# USB_Flash_Drive_Replacer.net
KiCad netlist of a schematic drawn in EasyEDA
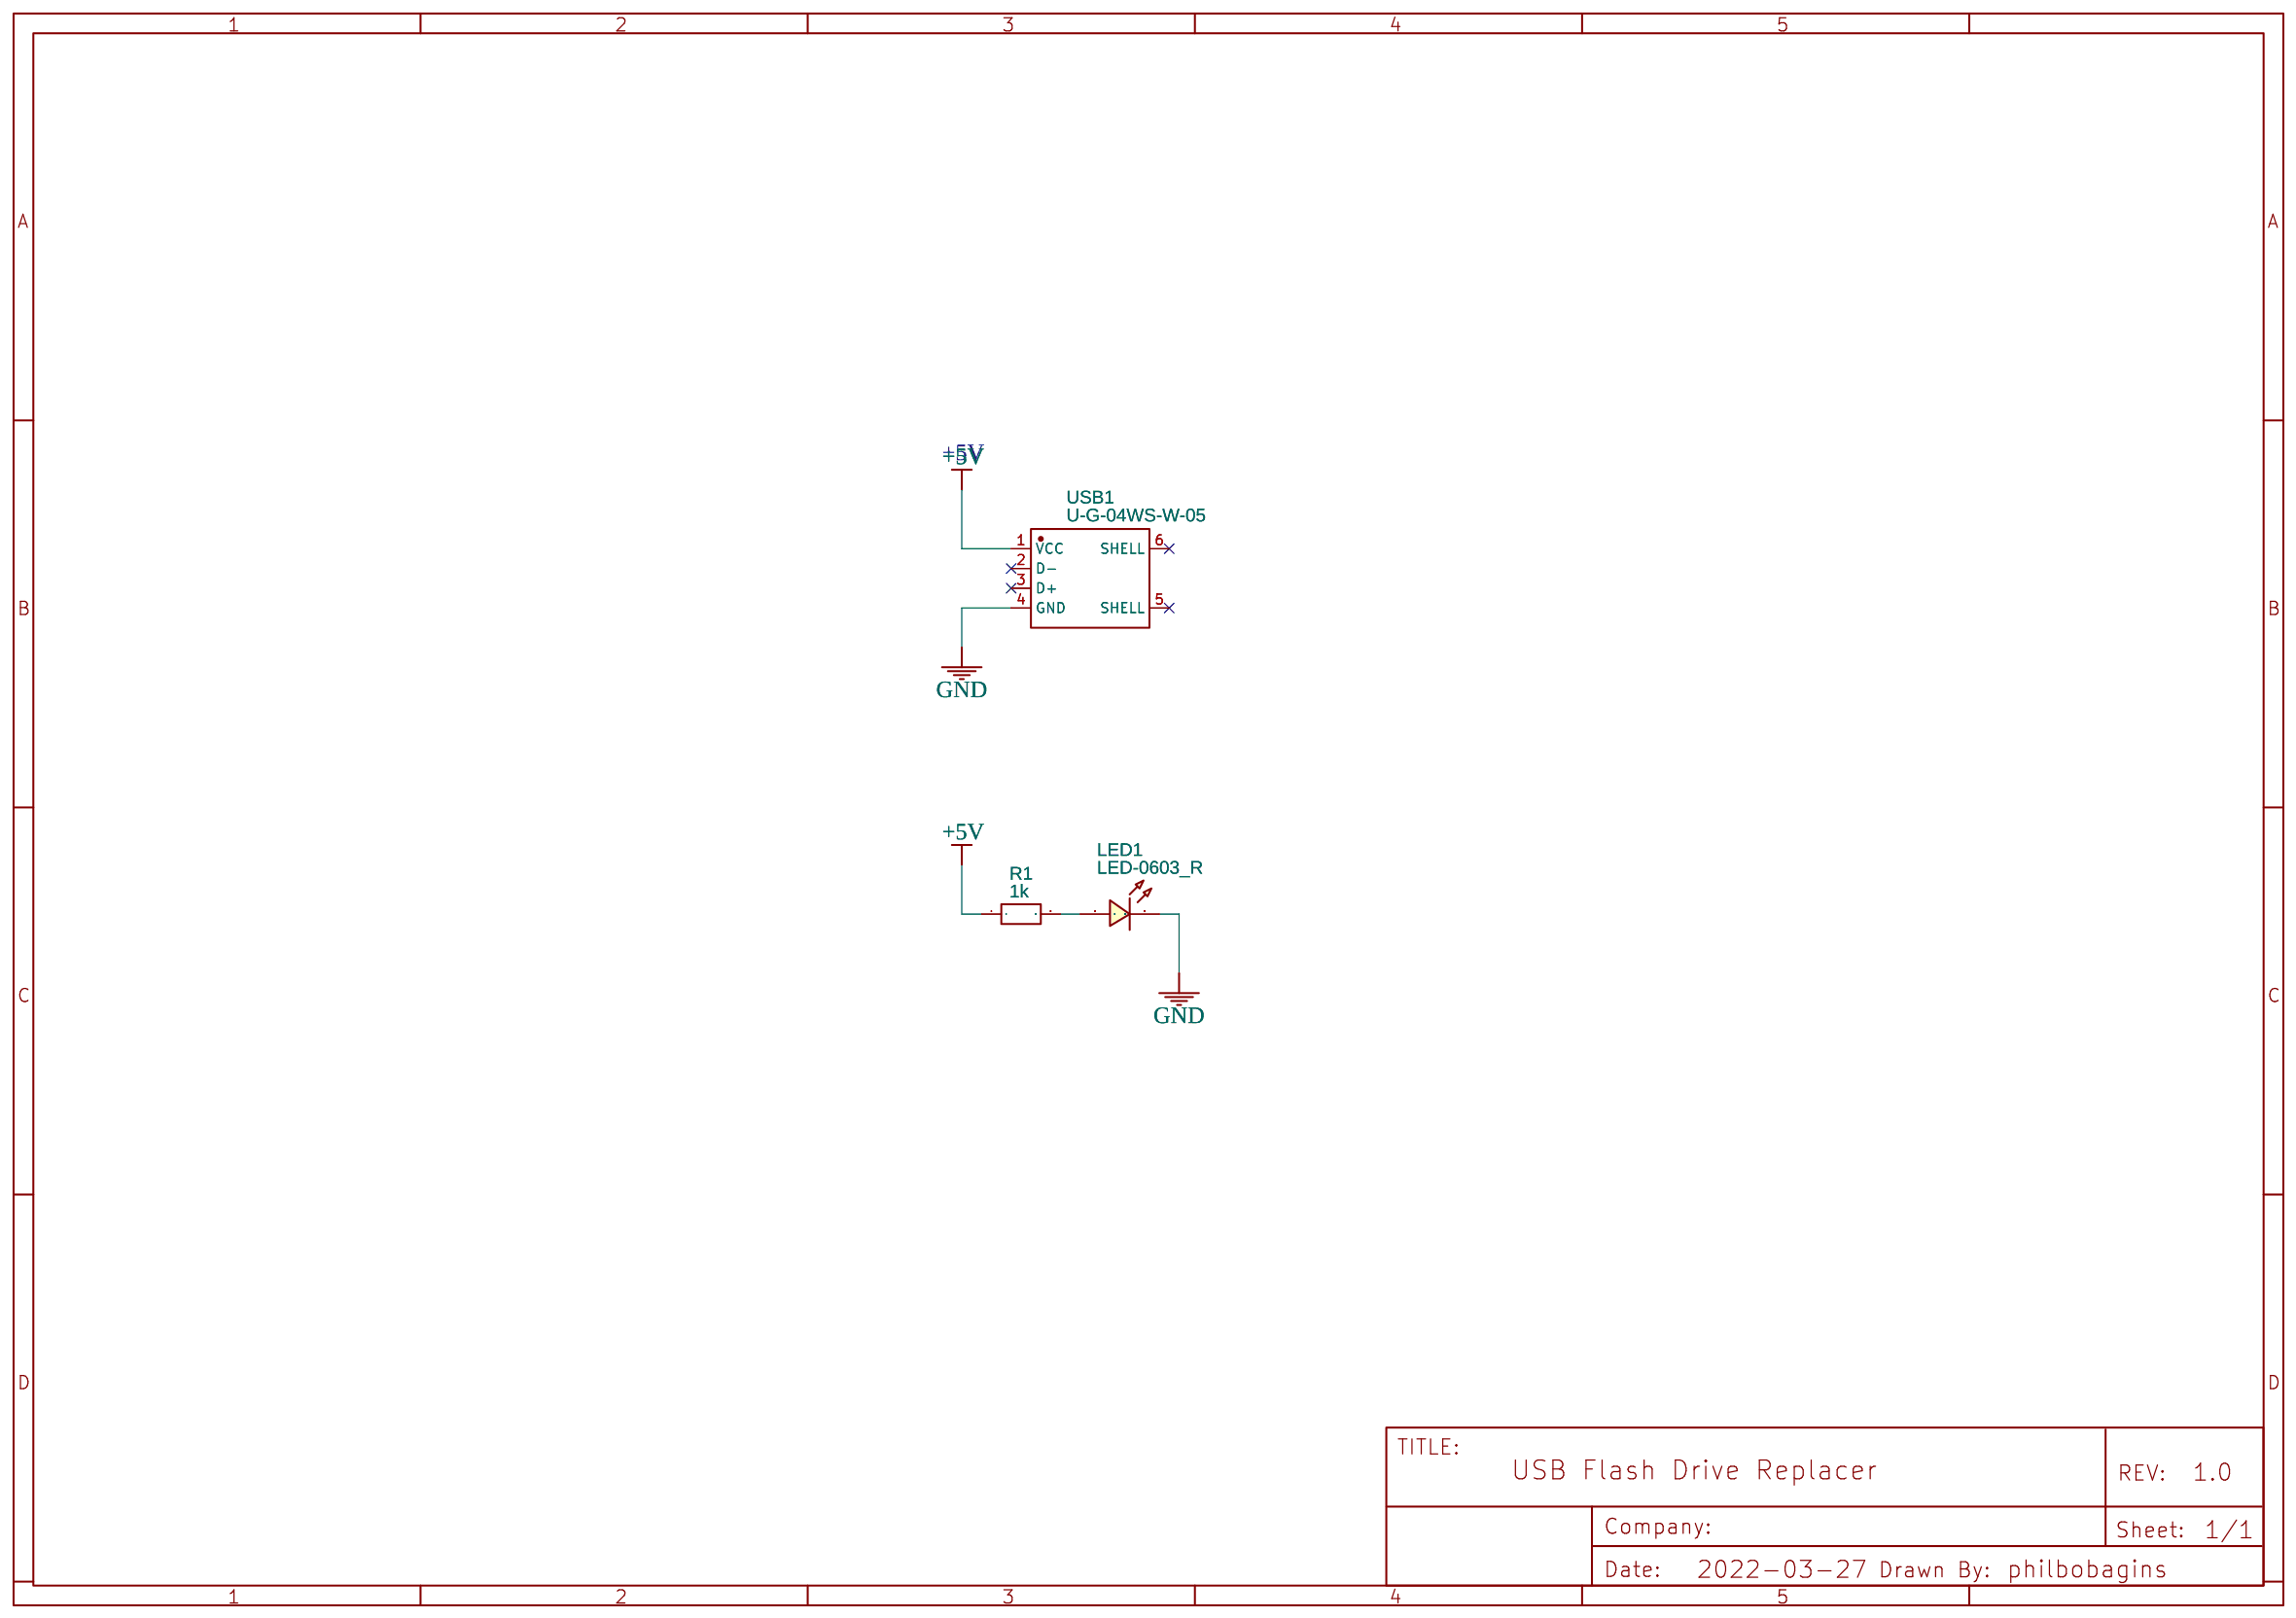
[diagram p0: schematic sheet]

(export (version "E")
  (design (tool "Eeschema 10.0.6"))
  (components
    (comp (ref "LED1")
      (value "LED-0603_R")
      (fields
        (field (name "BOM_Manufacturer Part") "19-217/R6C-AL1M2VY/3T")
        (field (name "BOM_Supplier Part") "C72044")
      )
      (libsource (lib "") (part "LED-0603_R"))
    )
    (comp (ref "R1")
      (value "1k")
      (fields
        (field (name "BOM_Manufacturer Part") "0805W8F1001T5E")
        (field (name "BOM_Supplier Part") "C17513")
      )
      (libsource (lib "") (part "R_0805_EU"))
    )
    (comp (ref "USB1")
      (value "U-G-04WS-W-05")
      (fields (field (name "BOM_Supplier Part") "C283547"))
      (libsource (lib "") (part "U-G-04WS-W-05"))
    )
  )
  (nets
    (net (code "1") (name "+5V") (class "Default")
      (node (ref "R1") (pin "1") (pinfunction "1_1") (pintype "unspecified"))
      (node (ref "USB1") (pin "1") (pinfunction "VCC_1") (pintype "unspecified"))
    )
    (net (code "2") (name "GND") (class "Default")
      (node (ref "LED1") (pin "2") (pinfunction "2_2") (pintype "unspecified"))
      (node (ref "USB1") (pin "4") (pinfunction "GND_4") (pintype "unspecified"))
    )
    (net (code "3") (name "Net-(LED1-Pad1)") (class "Default")
      (node (ref "LED1") (pin "1") (pinfunction "1_1") (pintype "unspecified"))
      (node (ref "R1") (pin "2") (pinfunction "2_2") (pintype "unspecified"))
    )
    (net (code "4") (name "unconnected-(USB1-D+-Pad3)") (class "Default")
      (node (ref "USB1") (pin "3") (pinfunction "D+_3") (pintype "unspecified+no_connect"))
    )
    (net (code "5") (name "unconnected-(USB1-D--Pad2)") (class "Default")
      (node (ref "USB1") (pin "2") (pinfunction "D-_2") (pintype "unspecified+no_connect"))
    )
    (net (code "6") (name "unconnected-(USB1-SHELL-Pad5)") (class "Default")
      (node (ref "USB1") (pin "5") (pinfunction "SHELL_5") (pintype "unspecified+no_connect"))
    )
    (net (code "7") (name "unconnected-(USB1-SHELL-Pad6)") (class "Default")
      (node (ref "USB1") (pin "6") (pinfunction "SHELL_6") (pintype "unspecified+no_connect"))
    )
  )
)
